# GPS_POWER.net
KiCad netlist of a schematic drawn in Altium Designer
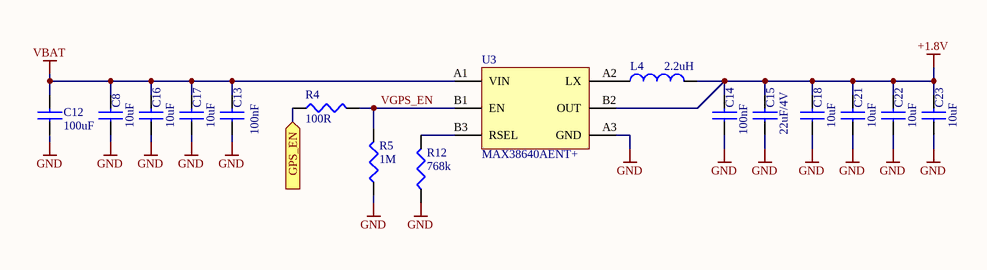
[diagram p0: GPS_POWER.SchDoc]

(export (version "E")
  (design (tool "Eeschema 10.0.6"))
  (components
    (comp (ref "C8")
      (value "10uF")
      (footprint "CAP0603")
      (description "Cap Ceramic 10uF 10V X5R 10% SMD 0603 85C Paper T/R")
      (fields
        (field (name "MANUFACTURER") "Samsung")
        (field (name "MANUFACTURER PART NUMBER") "CL10A106KP8NNNC")
      )
      (libsource (lib "Passive") (part "C - 10uF/10V"))
    )
    (comp (ref "C12")
      (value "100uF")
      (footprint "CAP0805")
      (description "Multilayer Ceramic Capacitors MLCC - SMD/SMT 0805 100uF 4volts *Derate Voltage/Temp")
      (fields
        (field (name "MANUFACTURER") "Murata")
        (field (name "MANUFACTURER PART NUMBER") "GRM21BR60G107ME15L")
      )
      (libsource (lib "Passive") (part "C - 100uF/0805"))
    )
    (comp (ref "C13")
      (value "100nF")
      (footprint "CAP0402")
      (fields
        (field (name "MANUFACTURER") "Multicomp")
        (field (name "MANUFACTURER PART NUMBER") "MC0402X104J160CT")
        (field (name "TOLERANCE") "5%")
      )
      (libsource (lib "Passive") (part "C - 100nF/0402"))
    )
    (comp (ref "C14")
      (value "100nF")
      (footprint "CAP0402")
      (fields
        (field (name "MANUFACTURER") "Multicomp")
        (field (name "MANUFACTURER PART NUMBER") "MC0402X104J160CT")
        (field (name "TOLERANCE") "5%")
      )
      (libsource (lib "Passive") (part "C - 100nF/0402"))
    )
    (comp (ref "C15")
      (value "22uF/4V")
      (footprint "CAP0603")
      (description "SMD Multilayer Ceramic Capacitor, 22 µF, 4 V, 0603 [1608 Metric], ± 20%, X5R, GRM Series")
      (fields
        (field (name "MANUFACTURER") "Samsung")
        (field (name "MANUFACTURER PART NUMBER") "GRM188R60G226MEA0D")
      )
      (libsource (lib "Passive") (part "C - 10uF/10V"))
    )
    (comp (ref "C16")
      (value "10uF")
      (footprint "CAP0603")
      (description "Cap Ceramic 10uF 10V X5R 10% SMD 0603 85C Paper T/R")
      (fields
        (field (name "MANUFACTURER") "Samsung")
        (field (name "MANUFACTURER PART NUMBER") "CL10A106KP8NNNC")
      )
      (libsource (lib "Passive") (part "C - 10uF/10V"))
    )
    (comp (ref "C17")
      (value "10uF")
      (footprint "CAP0603")
      (description "Cap Ceramic 10uF 10V X5R 10% SMD 0603 85C Paper T/R")
      (fields
        (field (name "MANUFACTURER") "Samsung")
        (field (name "MANUFACTURER PART NUMBER") "CL10A106KP8NNNC")
      )
      (libsource (lib "Passive") (part "C - 10uF/10V"))
    )
    (comp (ref "C18")
      (value "10uF")
      (footprint "CAP0603")
      (description "Cap Ceramic 10uF 10V X5R 10% SMD 0603 85C Paper T/R")
      (fields
        (field (name "MANUFACTURER") "Samsung")
        (field (name "MANUFACTURER PART NUMBER") "CL10A106KP8NNNC")
      )
      (libsource (lib "Passive") (part "C - 10uF/10V"))
    )
    (comp (ref "C21")
      (value "10uF")
      (footprint "CAP0603")
      (description "Cap Ceramic 10uF 10V X5R 10% SMD 0603 85C Paper T/R")
      (fields
        (field (name "MANUFACTURER") "Samsung")
        (field (name "MANUFACTURER PART NUMBER") "CL10A106KP8NNNC")
      )
      (libsource (lib "Passive") (part "C - 10uF/10V"))
    )
    (comp (ref "C22")
      (value "10uF")
      (footprint "CAP0603")
      (description "Cap Ceramic 10uF 10V X5R 10% SMD 0603 85C Paper T/R")
      (fields
        (field (name "MANUFACTURER") "Samsung")
        (field (name "MANUFACTURER PART NUMBER") "CL10A106KP8NNNC")
      )
      (libsource (lib "Passive") (part "C - 10uF/10V"))
    )
    (comp (ref "C23")
      (value "10uF")
      (footprint "CAP0603")
      (description "Cap Ceramic 10uF 10V X5R 10% SMD 0603 85C Paper T/R")
      (fields
        (field (name "MANUFACTURER") "Samsung")
        (field (name "MANUFACTURER PART NUMBER") "CL10A106KP8NNNC")
      )
      (libsource (lib "Passive") (part "C - 10uF/10V"))
    )
    (comp (ref "L4")
      (value "2.2uH")
      (footprint "IND2.3X1.7")
      (fields
        (field (name "MANUFACTURER") "Bourns")
        (field (name "MANUFACTURER PART NUMBER") "SRN2009T-2R2M")
        (field (name "IRNAS PART NO.") "/")
      )
      (libsource (lib "Passive") (part "L - 2.2 uH 900mA"))
    )
    (comp (ref "R4")
      (value "100R")
      (footprint "RES0402")
      (fields
        (field (name "MANUFACTURER") "Multicomp")
        (field (name "MANUFACTURER PART NUMBER") "MCMR04X1000FTL")
        (field (name "TOLERANCE") "1%")
      )
      (libsource (lib "Passive") (part "R - 100R/0402"))
    )
    (comp (ref "R5")
      (value "1M")
      (footprint "RES0402")
      (description "MCMR04X1004FTL RES, 1M, 1%, 0.0625W, 0402, THICK FILM")
      (fields
        (field (name "MANUFACTURER") "MULTICOMP")
        (field (name "MANUFACTURER PART NUMBER") "MC0063W060311M")
      )
      (libsource (lib "Passive") (part "R - 1M/0402"))
    )
    (comp (ref "R12")
      (value "768k")
      (footprint "RES0402")
      (description "RESISTOR, 0402, 768k, ANTI SULFURATION")
      (fields
        (field (name "MANUFACTURER") "Multicomp")
        (field (name "MANUFACTURER PART NUMBER") "MCMR04X000PTL")
      )
      (libsource (lib "Passive") (part "R - 768k/0402"))
    )
    (comp (ref "U3")
      (value "MAX38640AENT+")
      (footprint "WLP-6")
      (description "Switching Voltage Regulators Tiny 300nA nanoPower Buck converters in uDFN and WLP pacakges")
      (fields (field (name "MANUFACTURER") "ROHM") (field (name "MANUFACTURER PART NUMBER") "BD70522GUL"))
      (libsource (lib "Active") (part "V_SW - MAX38640AENT+"))
    )
  )
  (nets
    (net (code "1") (name "+1.8V") (class "Default")
      (node (ref "C14") (pin "2") (pinfunction "2_2") (pintype "passive"))
      (node (ref "C15") (pin "2") (pinfunction "2_2") (pintype "passive"))
      (node (ref "C18") (pin "2") (pinfunction "2_2") (pintype "passive"))
      (node (ref "C21") (pin "2") (pinfunction "2_2") (pintype "passive"))
      (node (ref "C22") (pin "2") (pinfunction "2_2") (pintype "passive"))
      (node (ref "C23") (pin "2") (pinfunction "2_2") (pintype "passive"))
      (node (ref "L4") (pin "2") (pinfunction "2_2") (pintype "passive"))
      (node (ref "U3") (pin "B2") (pinfunction "OUT_B2") (pintype "passive"))
    )
    (net (code "2") (name "/GPS_EN") (class "Default")
      (node (ref "R4") (pin "1") (pinfunction "1_1") (pintype "passive"))
    )
    (net (code "3") (name "/VGPS_EN") (class "Default")
      (node (ref "R4") (pin "2") (pinfunction "2_2") (pintype "passive"))
      (node (ref "R5") (pin "2") (pinfunction "2_2") (pintype "passive"))
      (node (ref "U3") (pin "B1") (pinfunction "EN_B1") (pintype "passive"))
    )
    (net (code "4") (name "GND") (class "Default")
      (node (ref "C12") (pin "1") (pinfunction "1_1") (pintype "passive"))
      (node (ref "C13") (pin "1") (pinfunction "1_1") (pintype "passive"))
      (node (ref "C14") (pin "1") (pinfunction "1_1") (pintype "passive"))
      (node (ref "C15") (pin "1") (pinfunction "1_1") (pintype "passive"))
      (node (ref "C16") (pin "1") (pinfunction "1_1") (pintype "passive"))
      (node (ref "C17") (pin "1") (pinfunction "1_1") (pintype "passive"))
      (node (ref "C18") (pin "1") (pinfunction "1_1") (pintype "passive"))
      (node (ref "C21") (pin "1") (pinfunction "1_1") (pintype "passive"))
      (node (ref "C22") (pin "1") (pinfunction "1_1") (pintype "passive"))
      (node (ref "C23") (pin "1") (pinfunction "1_1") (pintype "passive"))
      (node (ref "C8") (pin "1") (pinfunction "1_1") (pintype "passive"))
      (node (ref "R12") (pin "1") (pinfunction "1_1") (pintype "passive"))
      (node (ref "R5") (pin "1") (pinfunction "1_1") (pintype "passive"))
      (node (ref "U3") (pin "A3") (pinfunction "GND_A3") (pintype "passive"))
    )
    (net (code "5") (name "Net-(U3-LX)") (class "Default")
      (node (ref "L4") (pin "1") (pinfunction "1_1") (pintype "passive"))
      (node (ref "U3") (pin "A2") (pinfunction "LX_A2") (pintype "passive"))
    )
    (net (code "6") (name "Net-(U3-RSEL)") (class "Default")
      (node (ref "R12") (pin "2") (pinfunction "2_2") (pintype "passive"))
      (node (ref "U3") (pin "B3") (pinfunction "RSEL_B3") (pintype "passive"))
    )
    (net (code "7") (name "VBAT") (class "Default")
      (node (ref "C12") (pin "2") (pinfunction "2_2") (pintype "passive"))
      (node (ref "C13") (pin "2") (pinfunction "2_2") (pintype "passive"))
      (node (ref "C16") (pin "2") (pinfunction "2_2") (pintype "passive"))
      (node (ref "C17") (pin "2") (pinfunction "2_2") (pintype "passive"))
      (node (ref "C8") (pin "2") (pinfunction "2_2") (pintype "passive"))
      (node (ref "U3") (pin "A1") (pinfunction "VIN_A1") (pintype "passive"))
    )
  )
)
